# DC_DETECT.net
KiCad netlist of a schematic drawn in Altium Designer
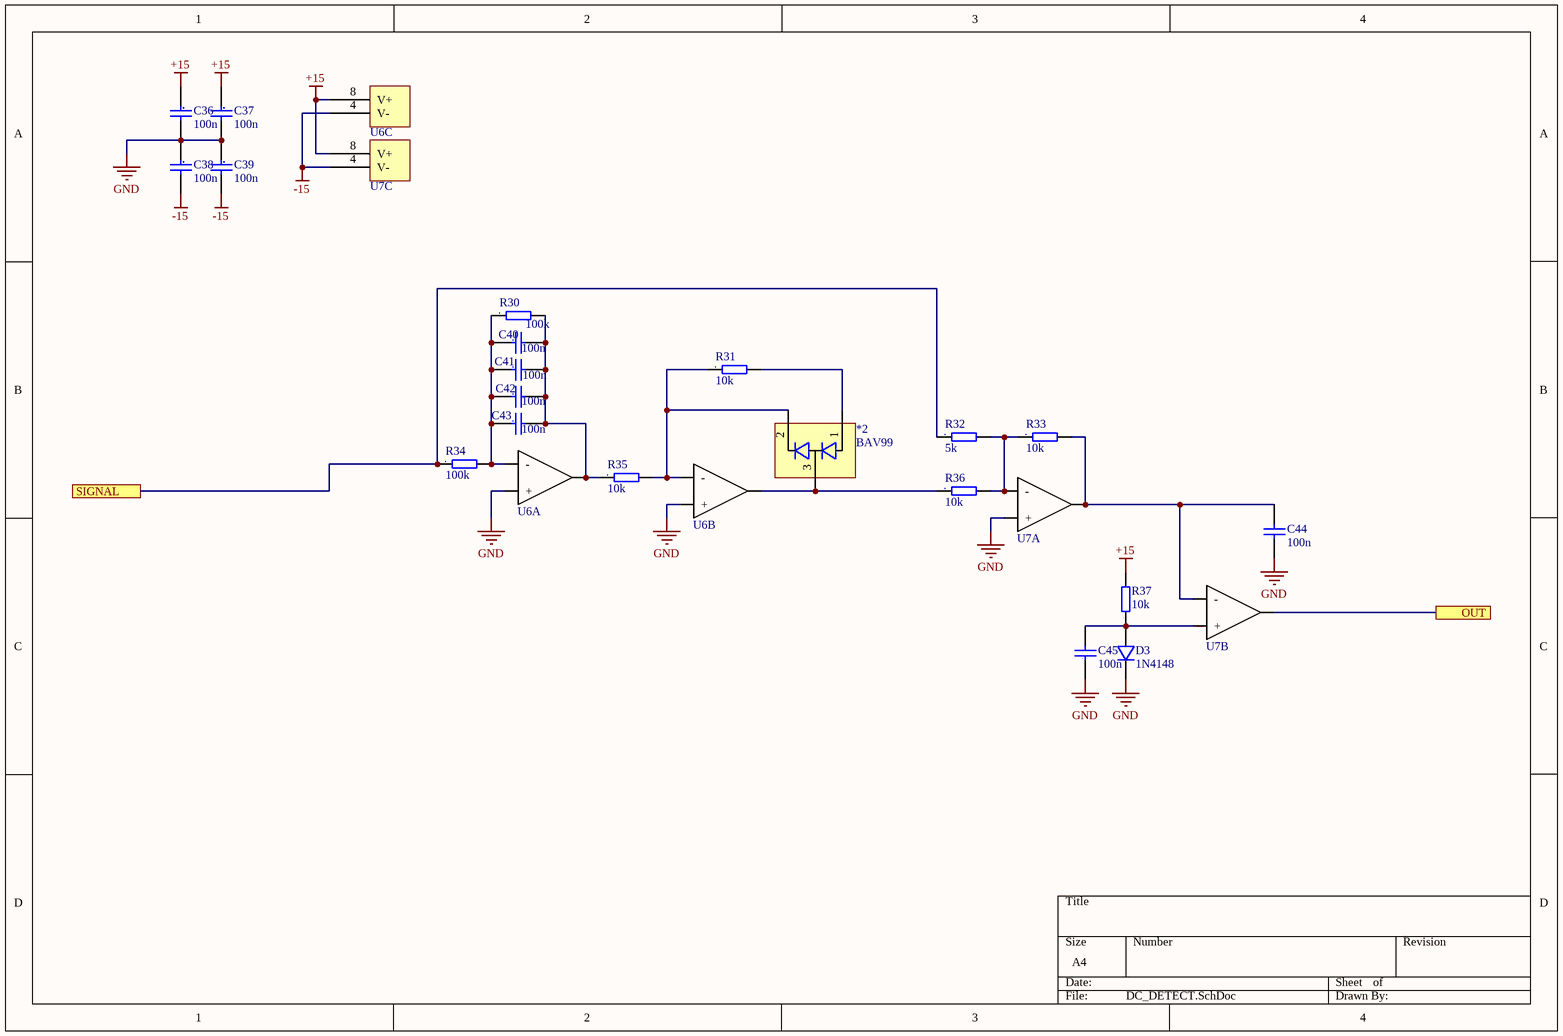
[diagram p0: DC_DETECT.SchDoc]

(export (version "E")
  (design (tool "Eeschema 10.0.6"))
  (components
    (comp (ref "*2") (value "BAV99") (footprint "SOT23_123_N") (libsource (lib "MyLib") (part "BAV99")))
    (comp (ref "C36") (value "100n") (footprint "C0603_N") (libsource (lib "MyLib") (part "CAP")))
    (comp (ref "C37") (value "100n") (footprint "C0603_N") (libsource (lib "MyLib") (part "CAP")))
    (comp (ref "C38") (value "100n") (footprint "C0603_N") (libsource (lib "MyLib") (part "CAP")))
    (comp (ref "C39") (value "100n") (footprint "C0603_N") (libsource (lib "MyLib") (part "CAP")))
    (comp (ref "C40") (value "100n") (footprint "C0603_N") (libsource (lib "MyLib") (part "CAP")))
    (comp (ref "C41") (value "100n") (footprint "C0603_N") (libsource (lib "MyLib") (part "CAP")))
    (comp (ref "C42") (value "100n") (footprint "C0603_N") (libsource (lib "MyLib") (part "CAP")))
    (comp (ref "C43") (value "100n") (footprint "C0603_N") (libsource (lib "MyLib") (part "CAP")))
    (comp (ref "C44") (value "100n") (footprint "C0603_N") (libsource (lib "MyLib") (part "CAP")))
    (comp (ref "C45") (value "100n") (footprint "C0603_N") (libsource (lib "MyLib") (part "CAP")))
    (comp (ref "D3") (value "1N4148") (footprint "SOD-80") (libsource (lib "MyLib") (part "DIODE")))
    (comp (ref "R30") (value "100k") (footprint "R0603_N") (libsource (lib "MyLib") (part "RES")))
    (comp (ref "R31") (value "10k") (footprint "R0603_N") (libsource (lib "MyLib") (part "RES")))
    (comp (ref "R32") (value "5k") (footprint "R0603_N") (libsource (lib "MyLib") (part "RES")))
    (comp (ref "R33") (value "10k") (footprint "R0603_N") (libsource (lib "MyLib") (part "RES")))
    (comp (ref "R34") (value "100k") (footprint "R0603_N") (libsource (lib "MyLib") (part "RES")))
    (comp (ref "R35") (value "10k") (footprint "R0603_N") (libsource (lib "MyLib") (part "RES")))
    (comp (ref "R36") (value "10k") (footprint "R0603_N") (libsource (lib "MyLib") (part "RES")))
    (comp (ref "R37") (value "10k") (footprint "R0603_N") (libsource (lib "MyLib") (part "RES")))
    (comp (ref "U6")
      (value "LM258")
      (footprint "SOIC-8")
      (description "Dual op. amp., 3..36V, Iq=300uA")
      (libsource (lib "MyLib") (part "LM258"))
    )
    (comp (ref "U7")
      (value "LM258")
      (footprint "SOIC-8")
      (description "Dual op. amp., 3..36V, Iq=300uA")
      (libsource (lib "MyLib") (part "LM258"))
    )
  )
  (nets
    (net (code "1") (name "+15") (class "Default")
      (node (ref "C36") (pin "1") (pinfunction "1_1") (pintype "passive"))
      (node (ref "C37") (pin "1") (pinfunction "1_1") (pintype "passive"))
      (node (ref "R37") (pin "2") (pinfunction "2_2") (pintype "passive"))
      (node (ref "U6") (pin "8") (pinfunction "V+_8") (pintype "passive"))
      (node (ref "U7") (pin "8") (pinfunction "V+_8") (pintype "passive"))
    )
    (net (code "2") (name "-15") (class "Default")
      (node (ref "C38") (pin "2") (pinfunction "2_2") (pintype "passive"))
      (node (ref "C39") (pin "2") (pinfunction "2_2") (pintype "passive"))
      (node (ref "U6") (pin "4") (pinfunction "V-_4") (pintype "passive"))
      (node (ref "U7") (pin "4") (pinfunction "V-_4") (pintype "passive"))
    )
    (net (code "3") (name "/OUT") (class "Default")
      (node (ref "U7") (pin "7") (pinfunction "Out_7") (pintype "passive"))
    )
    (net (code "4") (name "/SIGNAL") (class "Default")
      (node (ref "R32") (pin "1") (pinfunction "1_1") (pintype "passive"))
      (node (ref "R34") (pin "1") (pinfunction "1_1") (pintype "passive"))
    )
    (net (code "5") (name "GND") (class "Default")
      (node (ref "C36") (pin "2") (pinfunction "2_2") (pintype "passive"))
      (node (ref "C37") (pin "2") (pinfunction "2_2") (pintype "passive"))
      (node (ref "C38") (pin "1") (pinfunction "1_1") (pintype "passive"))
      (node (ref "C39") (pin "1") (pinfunction "1_1") (pintype "passive"))
      (node (ref "C44") (pin "1") (pinfunction "1_1") (pintype "passive"))
      (node (ref "C45") (pin "1") (pinfunction "1_1") (pintype "passive"))
      (node (ref "D3") (pin "C") (pinfunction "C_C") (pintype "passive"))
      (node (ref "U6") (pin "3") (pinfunction "+_3") (pintype "passive"))
      (node (ref "U6") (pin "5") (pinfunction "+_5") (pintype "passive"))
      (node (ref "U7") (pin "3") (pinfunction "+_3") (pintype "passive"))
    )
    (net (code "6") (name "Net-(*2-A)") (class "Default")
      (node (ref "*2") (pin "1") (pinfunction "A_1") (pintype "passive"))
      (node (ref "R31") (pin "2") (pinfunction "2_2") (pintype "passive"))
    )
    (net (code "7") (name "Net-(*2-C)") (class "Default")
      (node (ref "*2") (pin "2") (pinfunction "C_2") (pintype "passive"))
      (node (ref "R31") (pin "1") (pinfunction "1_1") (pintype "passive"))
      (node (ref "R35") (pin "2") (pinfunction "2_2") (pintype "passive"))
      (node (ref "U6") (pin "6") (pinfunction "-_6") (pintype "passive"))
    )
    (net (code "8") (name "Net-(*2-C{slash}A)") (class "Default")
      (node (ref "*2") (pin "3") (pinfunction "C/A_3") (pintype "passive"))
      (node (ref "R36") (pin "1") (pinfunction "1_1") (pintype "passive"))
      (node (ref "U6") (pin "7") (pinfunction "Out_7") (pintype "passive"))
    )
    (net (code "9") (name "Net-(U6A--)") (class "Default")
      (node (ref "C40") (pin "1") (pinfunction "1_1") (pintype "passive"))
      (node (ref "C41") (pin "1") (pinfunction "1_1") (pintype "passive"))
      (node (ref "C42") (pin "1") (pinfunction "1_1") (pintype "passive"))
      (node (ref "C43") (pin "1") (pinfunction "1_1") (pintype "passive"))
      (node (ref "R30") (pin "1") (pinfunction "1_1") (pintype "passive"))
      (node (ref "R34") (pin "2") (pinfunction "2_2") (pintype "passive"))
      (node (ref "U6") (pin "2") (pinfunction "-_2") (pintype "passive"))
    )
    (net (code "10") (name "Net-(U6A-Out)") (class "Default")
      (node (ref "C40") (pin "2") (pinfunction "2_2") (pintype "passive"))
      (node (ref "C41") (pin "2") (pinfunction "2_2") (pintype "passive"))
      (node (ref "C42") (pin "2") (pinfunction "2_2") (pintype "passive"))
      (node (ref "C43") (pin "2") (pinfunction "2_2") (pintype "passive"))
      (node (ref "R30") (pin "2") (pinfunction "2_2") (pintype "passive"))
      (node (ref "R35") (pin "1") (pinfunction "1_1") (pintype "passive"))
      (node (ref "U6") (pin "1") (pinfunction "Out_1") (pintype "passive"))
    )
    (net (code "11") (name "Net-(U7A--)") (class "Default")
      (node (ref "R32") (pin "2") (pinfunction "2_2") (pintype "passive"))
      (node (ref "R33") (pin "1") (pinfunction "1_1") (pintype "passive"))
      (node (ref "R36") (pin "2") (pinfunction "2_2") (pintype "passive"))
      (node (ref "U7") (pin "2") (pinfunction "-_2") (pintype "passive"))
    )
    (net (code "12") (name "Net-(U7A-Out)") (class "Default")
      (node (ref "C44") (pin "2") (pinfunction "2_2") (pintype "passive"))
      (node (ref "R33") (pin "2") (pinfunction "2_2") (pintype "passive"))
      (node (ref "U7") (pin "1") (pinfunction "Out_1") (pintype "passive"))
      (node (ref "U7") (pin "6") (pinfunction "-_6") (pintype "passive"))
    )
    (net (code "13") (name "Net-(U7B-+)") (class "Default")
      (node (ref "C45") (pin "2") (pinfunction "2_2") (pintype "passive"))
      (node (ref "D3") (pin "A") (pinfunction "A_A") (pintype "passive"))
      (node (ref "R37") (pin "1") (pinfunction "1_1") (pintype "passive"))
      (node (ref "U7") (pin "5") (pinfunction "+_5") (pintype "passive"))
    )
  )
)
